# MB1165.net
KiCad netlist of a schematic drawn in Altium Designer
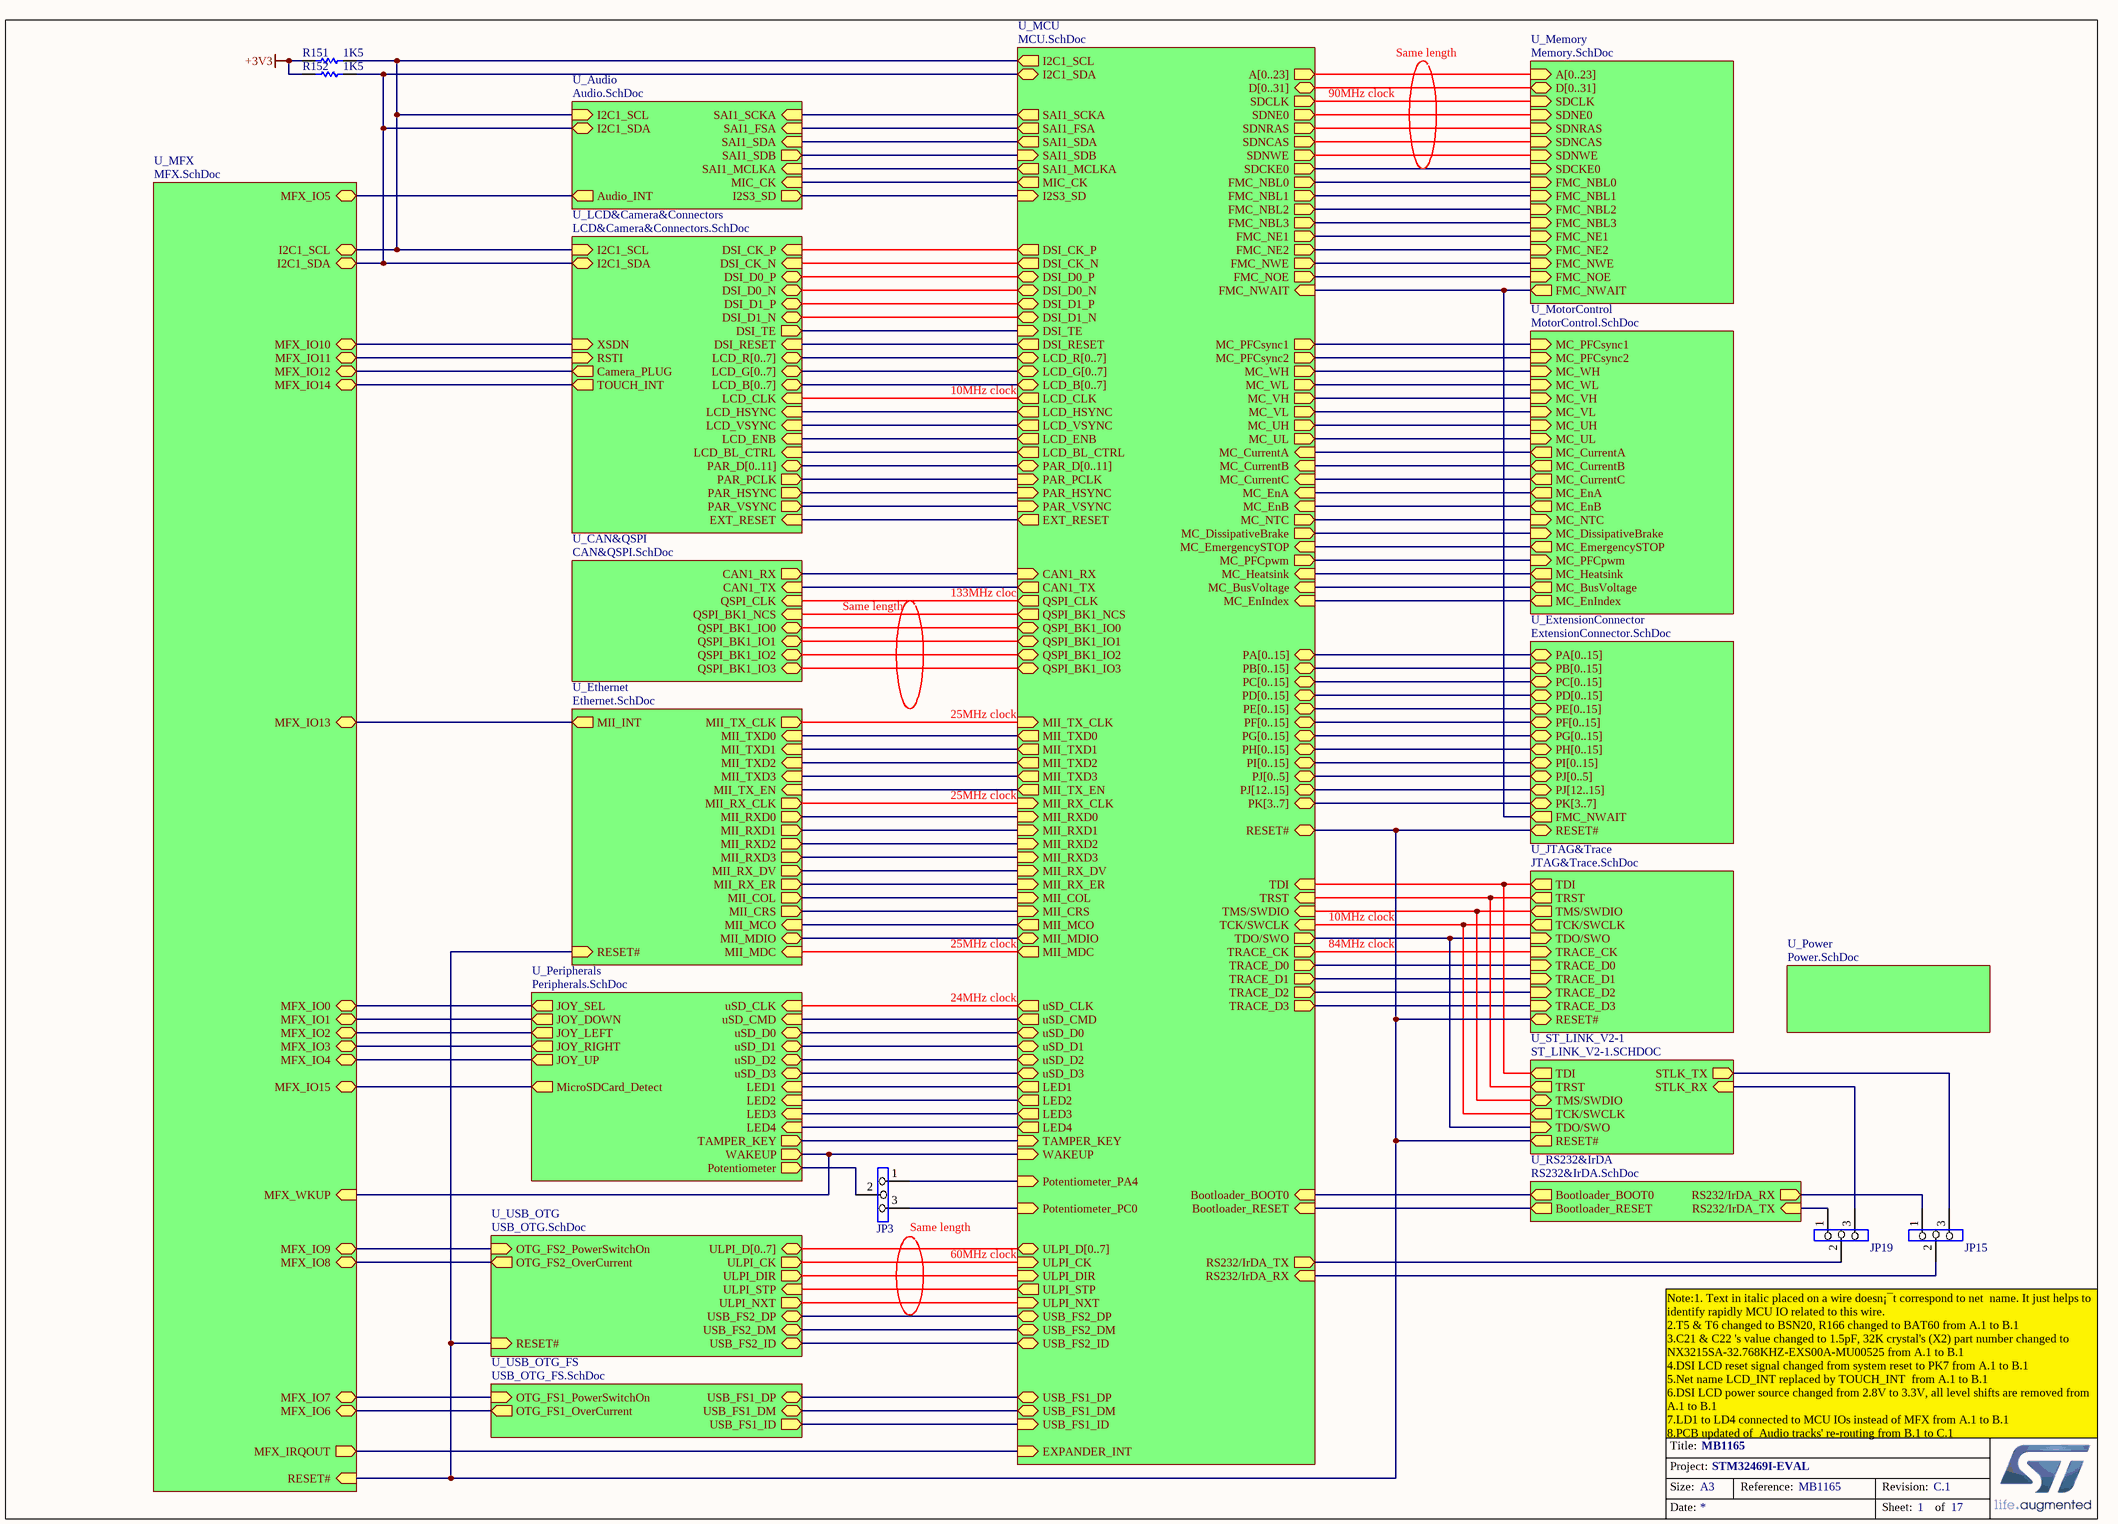
[diagram p0: MB1165.SchDoc]

(export (version "E")
  (design (tool "Eeschema 10.0.6"))
  (components
    (comp (ref "JP3") (value "~") (footprint "SIP3") (libsource (lib "STR910_SCHLIB") (part "Jumper3")))
    (comp (ref "JP15") (value "~") (footprint "SIP3") (libsource (lib "STR910_SCHLIB") (part "Jumper3")))
    (comp (ref "JP19") (value "~") (footprint "SIP3") (libsource (lib "STR910_SCHLIB") (part "Jumper3")))
    (comp (ref "R151")
      (value "1K5")
      (footprint "0603R")
      (description "Resistor")
      (fields (field (name "PUBLISHER") "Altium Limited"))
      (libsource (lib "Miscellaneous Devices") (part "Res1"))
    )
    (comp (ref "R152")
      (value "1K5")
      (footprint "0603R")
      (description "Resistor")
      (fields (field (name "PUBLISHER") "Altium Limited"))
      (libsource (lib "Miscellaneous Devices") (part "Res1"))
    )
  )
  (nets
    (net (code "1") (name "+3V3") (class "Default")
      (node (ref "R151") (pin "1") (pinfunction "1_1") (pintype "passive"))
      (node (ref "R152") (pin "1") (pinfunction "1_1") (pintype "passive"))
    )
    (net (code "28") (name "/I2C1_SCL") (class "Default")
      (node (ref "R151") (pin "2") (pinfunction "2_2") (pintype "passive"))
    )
    (net (code "29") (name "/I2C1_SDA") (class "Default")
      (node (ref "R152") (pin "2") (pinfunction "2_2") (pintype "passive"))
    )
    (net (code "112") (name "/Potentiometer") (class "Default")
      (node (ref "JP3") (pin "2") (pintype "passive"))
    )
    (net (code "113") (name "/Potentiometer_PA4") (class "Default")
      (node (ref "JP3") (pin "1") (pintype "passive"))
    )
    (net (code "114") (name "/Potentiometer_PC0") (class "Default")
      (node (ref "JP3") (pin "3") (pintype "passive"))
    )
    (net (code "122") (name "/RS232{slash}IrDA_RX") (class "Default")
      (node (ref "JP15") (pin "2") (pintype "passive"))
    )
    (net (code "123") (name "/RS232{slash}IrDA_RX_1") (class "Default")
      (node (ref "JP15") (pin "1") (pintype "passive"))
    )
    (net (code "124") (name "/RS232{slash}IrDA_TX") (class "Default")
      (node (ref "JP19") (pin "2") (pintype "passive"))
    )
    (net (code "125") (name "/RS232{slash}IrDA_TX_1") (class "Default")
      (node (ref "JP19") (pin "1") (pintype "passive"))
    )
    (net (code "137") (name "/STLK_RX") (class "Default") (node (ref "JP19") (pin "3") (pintype "passive")))
    (net (code "138") (name "/STLK_TX") (class "Default") (node (ref "JP15") (pin "3") (pintype "passive")))
  )
)
